# 1_2GHz_Comb_Gen_Driver.net
KiCad netlist of a schematic drawn in Altium Designer
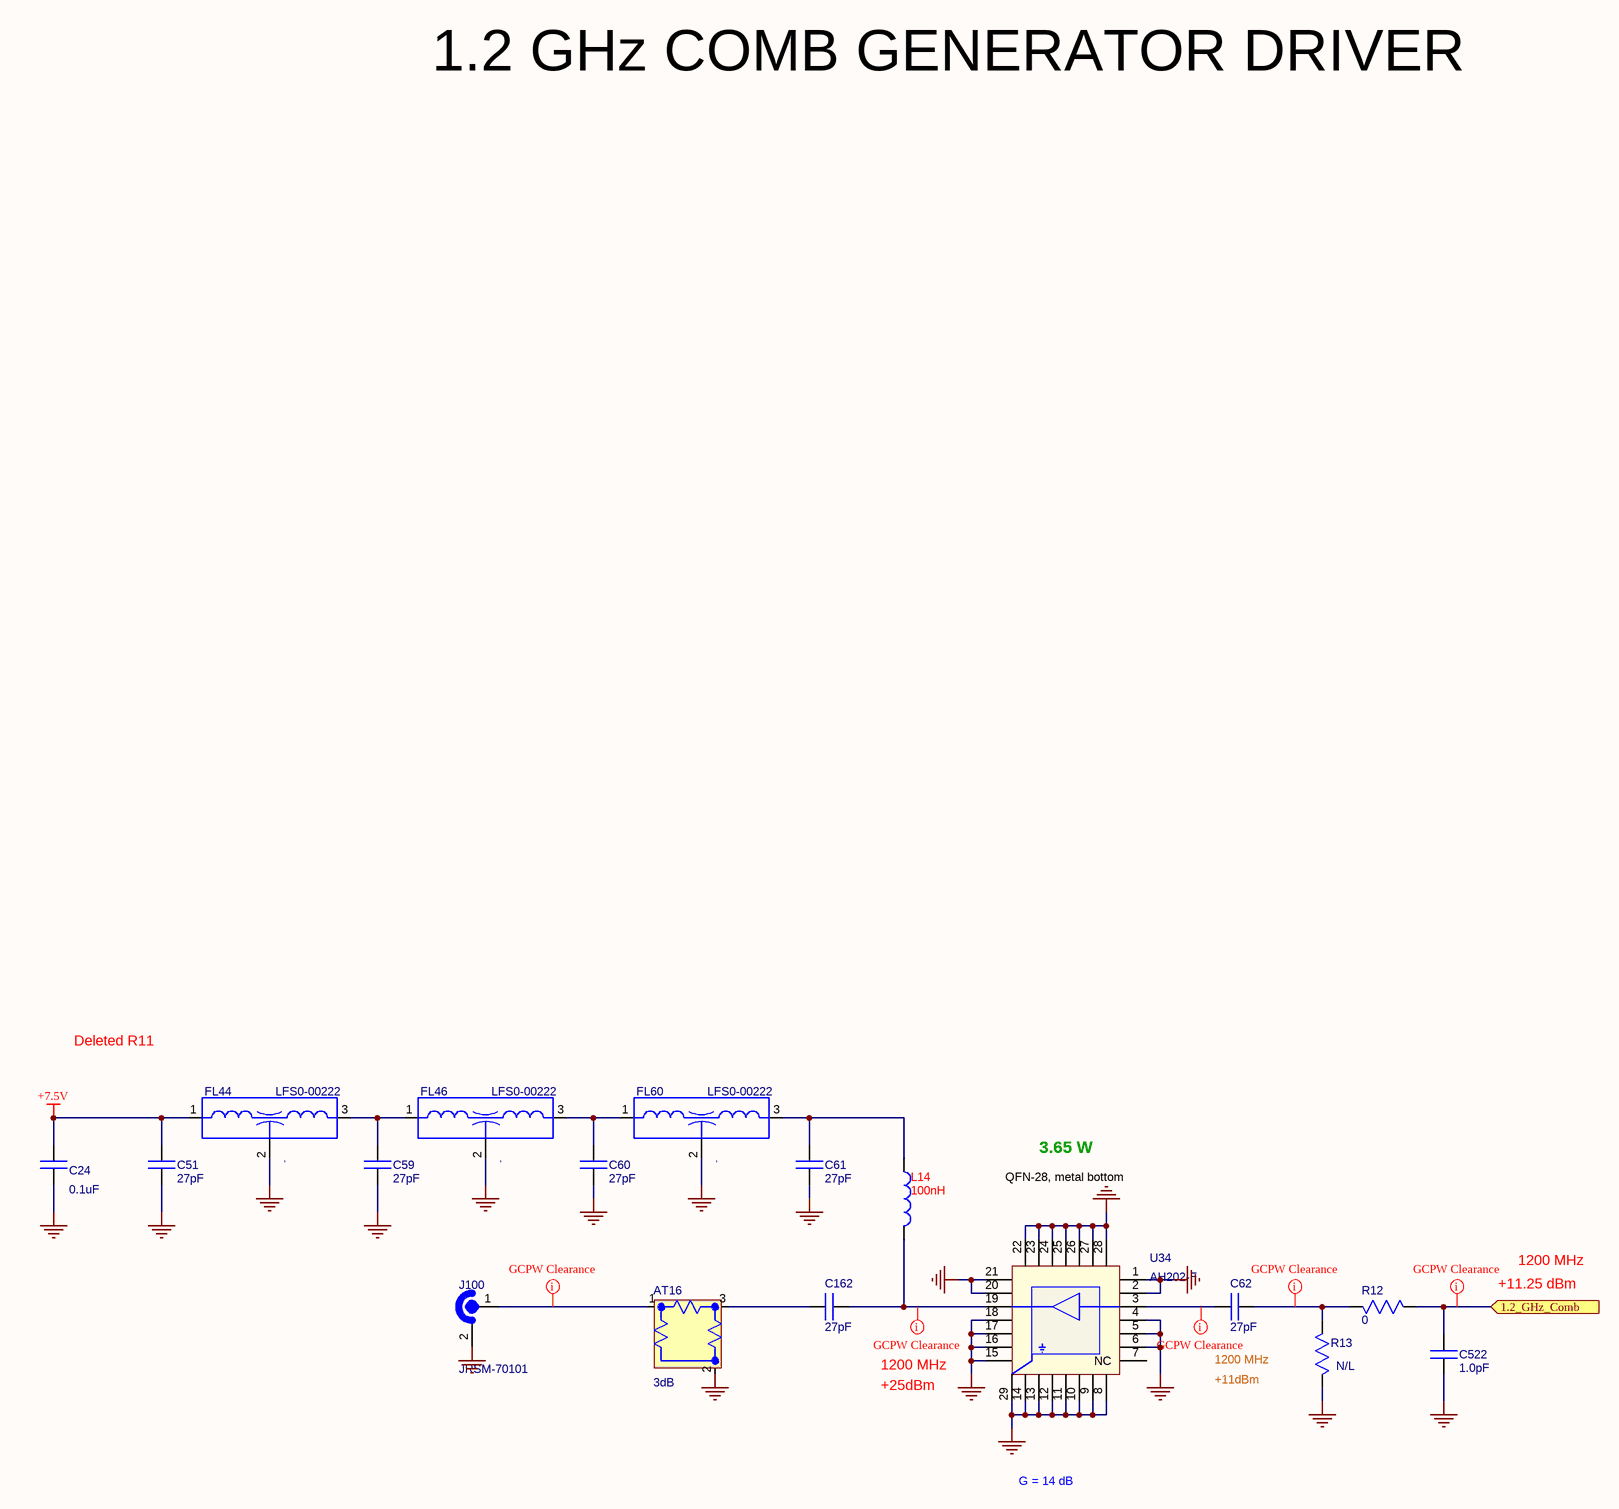
[diagram p0: 1.2GHz Comb Gen Driver.SchDoc]

(export (version "E")
  (design (tool "Eeschema 10.0.6"))
  (components
    (comp (ref "AT16")
      (value "3dB")
      (footprint "ATTN-IMS-0805")
      (description "PAD;CHIP;3dB;+/-.3dB;.08 x .05;50 OHM;FACE DOWN")
      (fields (field (name "APPROVED") "CL"))
      (libsource (lib "Giga-tronics") (part "MPFC-A1003"))
    )
    (comp (ref "C24")
      (value "0.1uF")
      (footprint "CAP-0603-H035-N")
      (description ".1UF;10%;X7R;16V;CHIP;0603")
      (fields (field (name "APPROVED") "CL"))
      (libsource (lib "Giga-tronics") (part "CK45-04100"))
    )
    (comp (ref "C51")
      (value "27pF")
      (footprint "CAP-0402-N")
      (description "27 PF;5%;COG;>50V;CHIP;0402")
      (fields (field (name "APPROVED") "CL"))
      (libsource (lib "Giga-tronics") (part "CK40-00270"))
    )
    (comp (ref "C59")
      (value "27pF")
      (footprint "CAP-0402-N")
      (description "27 PF;5%;COG;>50V;CHIP;0402")
      (fields (field (name "APPROVED") "CL"))
      (libsource (lib "Giga-tronics") (part "CK40-00270"))
    )
    (comp (ref "C60")
      (value "27pF")
      (footprint "CAP-0402-N")
      (description "27 PF;5%;COG;>50V;CHIP;0402")
      (fields (field (name "APPROVED") "CL"))
      (libsource (lib "Giga-tronics") (part "CK40-00270"))
    )
    (comp (ref "C61")
      (value "27pF")
      (footprint "CAP-0402-N")
      (description "27 PF;5%;COG;>50V;CHIP;0402")
      (fields (field (name "APPROVED") "CL"))
      (libsource (lib "Giga-tronics") (part "CK40-00270"))
    )
    (comp (ref "C62")
      (value "27pF")
      (footprint "CAP-0402-N")
      (description "27 PF;5%;COG;>50V;CHIP;0402")
      (fields (field (name "APPROVED") "CL"))
      (libsource (lib "Giga-tronics") (part "CK40-00270"))
    )
    (comp (ref "C162")
      (value "27pF")
      (footprint "CAP-0402-N")
      (description "27 PF;5%;COG;>50V;CHIP;0402")
      (fields (field (name "APPROVED") "CL"))
      (libsource (lib "Giga-tronics") (part "CK40-00270"))
    )
    (comp (ref "C522")
      (value "1.0pF")
      (footprint "CAP-0402-RF")
      (description "1.0 PF;200V;.05PF;HIGH Q;SMT;CERAMIC;0402")
      (fields (field (name "APPROVED") "CL"))
      (libsource (lib "Giga-tronics") (part "CK41-00010"))
    )
    (comp (ref "FL44")
      (value "Filter EMI 2200PF,1206")
      (footprint "FIL-NFE31P-1206-4P")
      (fields (field (name "G_PN") "LFS0-00222") (field (name "APPROVED") "CL"))
      (libsource (lib "Giga-tronics") (part "LFS0-00222"))
    )
    (comp (ref "FL46")
      (value "Filter EMI 2200PF,1206")
      (footprint "FIL-NFE31P-1206-4P")
      (fields (field (name "G_PN") "LFS0-00222") (field (name "APPROVED") "CL"))
      (libsource (lib "Giga-tronics") (part "LFS0-00222"))
    )
    (comp (ref "FL60")
      (value "Filter EMI 2200PF,1206")
      (footprint "FIL-NFE31P-1206-4P")
      (fields (field (name "G_PN") "LFS0-00222") (field (name "APPROVED") "CL"))
      (libsource (lib "Giga-tronics") (part "LFS0-00222"))
    )
    (comp (ref "J100")
      (value ".")
      (footprint "JRSM-70101")
      (description "SMPM FD MALE,STRAIGHT SMT, R/A COPLANAR, 4 PIN THRU-HOLE")
      (fields (field (name "G_PN") "JRSM-70101") (field (name "APPROVED") "CL"))
      (libsource (lib "Giga-tronics") (part "JRSM-70101"))
    )
    (comp (ref "L14")
      (value "100nH")
      (footprint "IND-1008HT")
      (description "INDUCTOR;100NH;5%;1.2G SRF;40Q@.25G;420mA;1008HT")
      (fields (field (name "APPROVED") "CL"))
      (libsource (lib "Giga-tronics") (part "LSA5-04100"))
    )
    (comp (ref "R12")
      (value "0")
      (footprint "RES-0402-N")
      (description "JUMPER;0 OHMS;SMT;0402")
      (fields (field (name "APPROVED") "CL"))
      (libsource (lib "Giga-tronics") (part "RK35-00000"))
    )
    (comp (ref "R13")
      (value "422 OHMS; 1%; .1W; 100PPM; FILM; CHIP; 0402")
      (footprint "RES-0402-N")
      (fields (field (name "NOLOAD") "N/L") (field (name "APPROVED") "CL"))
      (libsource (lib "Giga-tronics") (part "RK35-04220"))
    )
    (comp (ref "U34")
      (value "AMP;.05-2.2GHZ;+30DBM;11V;330MA;QFN-28 W/G")
      (footprint "QFN65P600X600X100-29")
      (fields (field (name "M_PN") "AH202-F") (field (name "APPROVED") "CL"))
      (libsource (lib "Giga-tronics") (part "MA17-10002"))
    )
  )
  (nets
    (net (code "1") (name "+7.5V") (class "Default")
      (node (ref "C24") (pin "1") (pintype "passive"))
      (node (ref "C51") (pin "1") (pintype "passive"))
      (node (ref "FL44") (pin "1") (pinfunction "IN_1") (pintype "passive"))
    )
    (net (code "2") (name "/1.2_GHz_Comb") (class "Default")
      (node (ref "C522") (pin "2") (pintype "passive"))
      (node (ref "R12") (pin "1") (pintype "passive"))
    )
    (net (code "3") (name "GND") (class "Default")
      (node (ref "AT16") (pin "2") (pinfunction "GND_2") (pintype "power_in"))
      (node (ref "C24") (pin "2") (pintype "passive"))
      (node (ref "C51") (pin "2") (pintype "passive"))
      (node (ref "C522") (pin "1") (pintype "passive"))
      (node (ref "C59") (pin "2") (pintype "passive"))
      (node (ref "C60") (pin "2") (pintype "passive"))
      (node (ref "C61") (pin "2") (pintype "passive"))
      (node (ref "FL44") (pin "2") (pinfunction "GND_2") (pintype "passive"))
      (node (ref "FL46") (pin "2") (pinfunction "GND_2") (pintype "passive"))
      (node (ref "FL60") (pin "2") (pinfunction "GND_2") (pintype "passive"))
      (node (ref "J100") (pin "2") (pinfunction "GND_2") (pintype "passive"))
      (node (ref "R13") (pin "2") (pintype "passive"))
      (node (ref "U34") (pin "1") (pinfunction "GND_1") (pintype "passive"))
      (node (ref "U34") (pin "10") (pinfunction "GND_10") (pintype "passive"))
      (node (ref "U34") (pin "11") (pinfunction "GND_11") (pintype "passive"))
      (node (ref "U34") (pin "12") (pinfunction "GND_12") (pintype "passive"))
      (node (ref "U34") (pin "13") (pinfunction "GND_13") (pintype "passive"))
      (node (ref "U34") (pin "14") (pinfunction "GND_14") (pintype "passive"))
      (node (ref "U34") (pin "15") (pinfunction "GND_15") (pintype "passive"))
      (node (ref "U34") (pin "16") (pinfunction "GND_16") (pintype "passive"))
      (node (ref "U34") (pin "17") (pinfunction "GND_17") (pintype "passive"))
      (node (ref "U34") (pin "18") (pinfunction "GND_18") (pintype "passive"))
      (node (ref "U34") (pin "2") (pinfunction "GND_2") (pintype "passive"))
      (node (ref "U34") (pin "20") (pinfunction "GND_20") (pintype "passive"))
      (node (ref "U34") (pin "21") (pinfunction "GND_21") (pintype "passive"))
      (node (ref "U34") (pin "22") (pinfunction "GND_22") (pintype "passive"))
      (node (ref "U34") (pin "23") (pinfunction "GND_23") (pintype "passive"))
      (node (ref "U34") (pin "24") (pinfunction "GND_24") (pintype "passive"))
      (node (ref "U34") (pin "25") (pinfunction "GND_25") (pintype "passive"))
      (node (ref "U34") (pin "26") (pinfunction "GND_26") (pintype "passive"))
      (node (ref "U34") (pin "27") (pinfunction "GND_27") (pintype "passive"))
      (node (ref "U34") (pin "28") (pinfunction "GND_28") (pintype "passive"))
      (node (ref "U34") (pin "29") (pinfunction "GND_29") (pintype "passive"))
      (node (ref "U34") (pin "4") (pinfunction "GND_4") (pintype "passive"))
      (node (ref "U34") (pin "5") (pinfunction "GND_5") (pintype "passive"))
      (node (ref "U34") (pin "6") (pinfunction "GND_6") (pintype "passive"))
      (node (ref "U34") (pin "8") (pinfunction "GND_8") (pintype "passive"))
      (node (ref "U34") (pin "9") (pinfunction "GND_9") (pintype "passive"))
    )
    (net (code "4") (name "Net-(AT16-IN{slash}OUT-Pad3)") (class "Default")
      (node (ref "AT16") (pin "3") (pinfunction "IN/OUT_3") (pintype "passive"))
      (node (ref "C162") (pin "1") (pintype "passive"))
    )
    (net (code "5") (name "Net-(C62-Pad1)") (class "Default")
      (node (ref "C62") (pin "1") (pintype "passive"))
      (node (ref "R12") (pin "2") (pintype "passive"))
      (node (ref "R13") (pin "1") (pintype "passive"))
    )
    (net (code "6") (name "Net-(C162-Pad2)") (class "Default")
      (node (ref "C162") (pin "2") (pintype "passive"))
      (node (ref "L14") (pin "2") (pinfunction "2_2") (pintype "passive"))
      (node (ref "U34") (pin "19") (pinfunction "GND_19") (pintype "passive"))
    )
    (net (code "7") (name "Net-(FL44-OUT)") (class "Default")
      (node (ref "C59") (pin "1") (pintype "passive"))
      (node (ref "FL44") (pin "3") (pinfunction "OUT_3") (pintype "passive"))
      (node (ref "FL46") (pin "1") (pinfunction "IN_1") (pintype "passive"))
    )
    (net (code "8") (name "Net-(FL46-OUT)") (class "Default")
      (node (ref "C60") (pin "1") (pintype "passive"))
      (node (ref "FL46") (pin "3") (pinfunction "OUT_3") (pintype "passive"))
      (node (ref "FL60") (pin "1") (pinfunction "IN_1") (pintype "passive"))
    )
    (net (code "9") (name "Net-(FL60-OUT)") (class "Default")
      (node (ref "C61") (pin "1") (pintype "passive"))
      (node (ref "FL60") (pin "3") (pinfunction "OUT_3") (pintype "passive"))
      (node (ref "L14") (pin "1") (pinfunction "1_1") (pintype "passive"))
    )
    (net (code "10") (name "Net-(J100-CNTR)") (class "Default")
      (node (ref "AT16") (pin "1") (pinfunction "IN/OUT_1") (pintype "passive"))
      (node (ref "J100") (pin "1") (pinfunction "CNTR_1") (pintype "passive"))
    )
    (net (code "11") (name "Net-(U34-In)") (class "Default")
      (node (ref "C62") (pin "2") (pintype "passive"))
      (node (ref "U34") (pin "3") (pinfunction "In_3") (pintype "passive"))
    )
    (net (code "12") (name "unconnected-(U34-NC-Pad7)") (class "Default")
      (node (ref "U34") (pin "7") (pinfunction "NC_7") (pintype "passive"))
    )
  )
)
